# audioamp.net
KiCad netlist of a schematic drawn in EAGLE
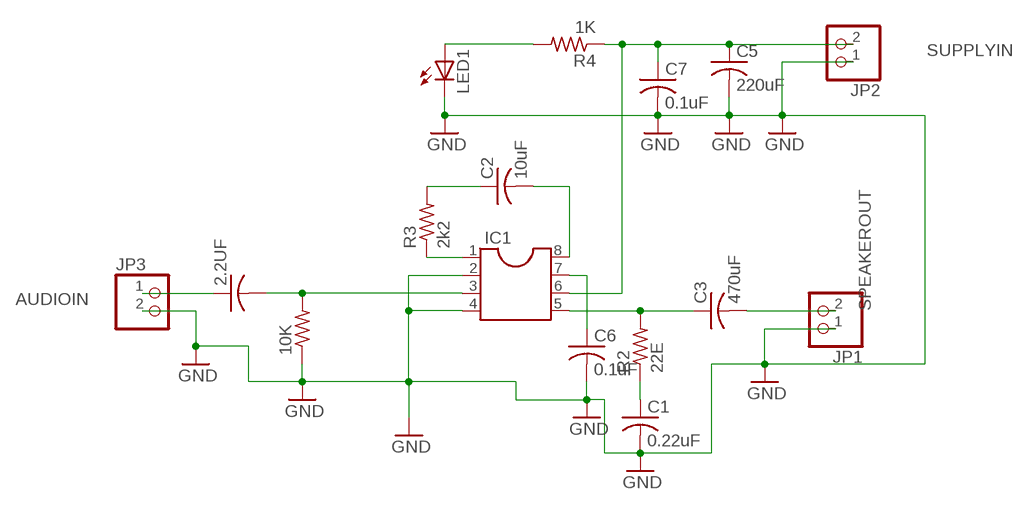
[diagram p0: schematic, sheet 1]

(export (version "E")
  (design (tool "Eeschema 10.0.6"))
  (components
    (comp (ref "2.2UF")
      (value "C-US025-030X050")
      (footprint "eagle-import:C025-030X050")
      (libsource (lib "eagle-import") (part "C-US025-030X050"))
    )
    (comp (ref "10K")
      (value "R-US_0207/10")
      (footprint "eagle-import:0207_10")
      (libsource (lib "eagle-import") (part "R-US_0207/10"))
    )
    (comp (ref "C1")
      (value "0.22uF")
      (footprint "eagle-import:C025-030X050")
      (libsource (lib "eagle-import") (part "C-US025-030X050"))
    )
    (comp (ref "C2")
      (value "10uF")
      (footprint "eagle-import:C025-030X050")
      (libsource (lib "eagle-import") (part "C-US025-030X050"))
    )
    (comp (ref "C3")
      (value "470uF")
      (footprint "eagle-import:C025-030X050")
      (libsource (lib "eagle-import") (part "C-US025-030X050"))
    )
    (comp (ref "C5")
      (value "220uF")
      (footprint "eagle-import:C025-030X050")
      (libsource (lib "eagle-import") (part "C-US025-030X050"))
    )
    (comp (ref "C6")
      (value "0.1uF")
      (footprint "eagle-import:C025-030X050")
      (libsource (lib "eagle-import") (part "C-US025-030X050"))
    )
    (comp (ref "C7")
      (value "0.1uF")
      (footprint "eagle-import:C025-030X050")
      (libsource (lib "eagle-import") (part "C-US025-030X050"))
    )
    (comp (ref "IC1")
      (value "DIL8")
      (footprint "eagle-import:DIL08")
      (libsource (lib "eagle-import") (part "DIL8"))
    )
    (comp (ref "JP1")
      (value "PINHD-1X2")
      (footprint "eagle-import:1X02")
      (libsource (lib "eagle-import") (part "PINHD-1X2"))
    )
    (comp (ref "JP2")
      (value "PINHD-1X2")
      (footprint "eagle-import:1X02")
      (libsource (lib "eagle-import") (part "PINHD-1X2"))
    )
    (comp (ref "JP3")
      (value "PINHD-1X2")
      (footprint "eagle-import:1X02")
      (libsource (lib "eagle-import") (part "PINHD-1X2"))
    )
    (comp (ref "LED1")
      (value "LED5MM")
      (footprint "eagle-import:LED5MM")
      (libsource (lib "eagle-import") (part "LED5MM"))
    )
    (comp (ref "R2")
      (value "22E")
      (footprint "eagle-import:0207_10")
      (libsource (lib "eagle-import") (part "R-US_0207/10"))
    )
    (comp (ref "R3")
      (value "2k2")
      (footprint "eagle-import:0207_10")
      (libsource (lib "eagle-import") (part "R-US_0207/10"))
    )
    (comp (ref "R4")
      (value "1K")
      (footprint "eagle-import:0207_10")
      (libsource (lib "eagle-import") (part "R-US_0207/10"))
    )
  )
  (nets
    (net (code "1") (name "/AUDIOIN") (class "Default")
      (node (ref "2.2UF") (pin "1") (pinfunction "1_1") (pintype "passive"))
      (node (ref "JP3") (pin "1") (pinfunction "1_1") (pintype "passive"))
    )
    (net (code "2") (name "/SPEAKEROUT") (class "Default")
      (node (ref "C3") (pin "2") (pinfunction "2_2") (pintype "passive"))
      (node (ref "JP1") (pin "2") (pinfunction "2_2") (pintype "passive"))
    )
    (net (code "3") (name "/SUPPLYIN") (class "Default")
      (node (ref "C5") (pin "1") (pinfunction "1_1") (pintype "passive"))
      (node (ref "C7") (pin "1") (pinfunction "1_1") (pintype "passive"))
      (node (ref "IC1") (pin "6") (pinfunction "6_6") (pintype "passive"))
      (node (ref "JP2") (pin "2") (pinfunction "2_2") (pintype "passive"))
      (node (ref "R4") (pin "1") (pinfunction "1_1") (pintype "passive"))
    )
    (net (code "4") (name "GND") (class "Default")
      (node (ref "10K") (pin "1") (pinfunction "1_1") (pintype "passive"))
      (node (ref "C1") (pin "2") (pinfunction "2_2") (pintype "passive"))
      (node (ref "C5") (pin "2") (pinfunction "2_2") (pintype "passive"))
      (node (ref "C6") (pin "2") (pinfunction "2_2") (pintype "passive"))
      (node (ref "C7") (pin "2") (pinfunction "2_2") (pintype "passive"))
      (node (ref "IC1") (pin "2") (pinfunction "2_2") (pintype "passive"))
      (node (ref "IC1") (pin "4") (pinfunction "4_4") (pintype "passive"))
      (node (ref "JP1") (pin "1") (pinfunction "1_1") (pintype "passive"))
      (node (ref "JP2") (pin "1") (pinfunction "1_1") (pintype "passive"))
      (node (ref "JP3") (pin "2") (pinfunction "2_2") (pintype "passive"))
      (node (ref "LED1") (pin "K") (pinfunction "C_K") (pintype "passive"))
    )
    (net (code "5") (name "Net-(10K-Pad2)") (class "Default")
      (node (ref "10K") (pin "2") (pinfunction "2_2") (pintype "passive"))
      (node (ref "2.2UF") (pin "2") (pinfunction "2_2") (pintype "passive"))
      (node (ref "IC1") (pin "3") (pinfunction "3_3") (pintype "passive"))
    )
    (net (code "6") (name "Net-(C1-Pad1)") (class "Default")
      (node (ref "C1") (pin "1") (pinfunction "1_1") (pintype "passive"))
      (node (ref "R2") (pin "1") (pinfunction "1_1") (pintype "passive"))
    )
    (net (code "7") (name "Net-(C2-Pad1)") (class "Default")
      (node (ref "C2") (pin "1") (pinfunction "1_1") (pintype "passive"))
      (node (ref "R3") (pin "2") (pinfunction "2_2") (pintype "passive"))
    )
    (net (code "8") (name "Net-(C2-Pad2)") (class "Default")
      (node (ref "C2") (pin "2") (pinfunction "2_2") (pintype "passive"))
      (node (ref "IC1") (pin "8") (pinfunction "8_8") (pintype "passive"))
    )
    (net (code "9") (name "Net-(C3-Pad1)") (class "Default")
      (node (ref "C3") (pin "1") (pinfunction "1_1") (pintype "passive"))
      (node (ref "IC1") (pin "5") (pinfunction "5_5") (pintype "passive"))
      (node (ref "R2") (pin "2") (pinfunction "2_2") (pintype "passive"))
    )
    (net (code "10") (name "Net-(C6-Pad1)") (class "Default")
      (node (ref "C6") (pin "1") (pinfunction "1_1") (pintype "passive"))
      (node (ref "IC1") (pin "7") (pinfunction "7_7") (pintype "passive"))
    )
    (net (code "11") (name "Net-(IC1-Pad1)") (class "Default")
      (node (ref "IC1") (pin "1") (pinfunction "1_1") (pintype "passive"))
      (node (ref "R3") (pin "1") (pinfunction "1_1") (pintype "passive"))
    )
    (net (code "12") (name "Net-(LED1-PadA)") (class "Default")
      (node (ref "LED1") (pin "A") (pinfunction "A_A") (pintype "passive"))
      (node (ref "R4") (pin "2") (pinfunction "2_2") (pintype "passive"))
    )
  )
)
